# I2C_HANDLER.net
KiCad netlist of a schematic drawn in Altium Designer
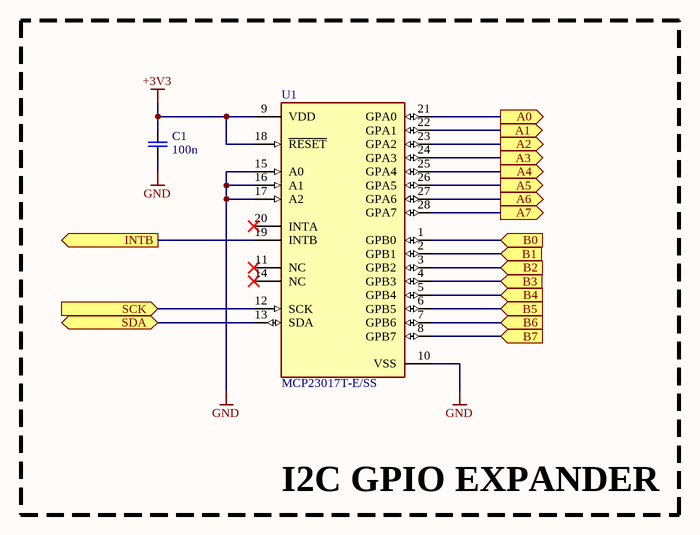
[diagram p0: I2C_HANDLER.SchDoc]

(export (version "E")
  (design (tool "Eeschema 10.0.6"))
  (components
    (comp (ref "C1")
      (value "100n")
      (footprint "C0603")
      (description "Generic 0603 SMD Ceramic Capacitor")
      (libsource (lib "PolSl Racing - Electrical") (part "Capacitor"))
    )
    (comp (ref "U1")
      (value "MCP23017T-E/SS")
      (footprint "FP-C04-073-IPC_C")
      (description "IC I/O EXPANDER 16BIT I2C 28SSOP")
      (libsource (lib "Altium Content Vault") (part "fef0bad8f325ed3b0116f589d195a7e"))
    )
  )
  (nets
    (net (code "1") (name "+3V3") (class "Default")
      (node (ref "C1") (pin "2") (pinfunction "2_2") (pintype "passive"))
      (node (ref "U1") (pin "18") (pinfunction "~{RESET}_18") (pintype "input"))
      (node (ref "U1") (pin "9") (pinfunction "VDD_9") (pintype "power_in"))
    )
    (net (code "2") (name "/A0") (class "Default")
      (node (ref "U1") (pin "21") (pinfunction "GPA0_21") (pintype "bidirectional"))
    )
    (net (code "3") (name "/A1") (class "Default")
      (node (ref "U1") (pin "22") (pinfunction "GPA1_22") (pintype "bidirectional"))
    )
    (net (code "4") (name "/A2") (class "Default")
      (node (ref "U1") (pin "23") (pinfunction "GPA2_23") (pintype "bidirectional"))
    )
    (net (code "5") (name "/A3") (class "Default")
      (node (ref "U1") (pin "24") (pinfunction "GPA3_24") (pintype "bidirectional"))
    )
    (net (code "6") (name "/A4") (class "Default")
      (node (ref "U1") (pin "25") (pinfunction "GPA4_25") (pintype "bidirectional"))
    )
    (net (code "7") (name "/A5") (class "Default")
      (node (ref "U1") (pin "26") (pinfunction "GPA5_26") (pintype "bidirectional"))
    )
    (net (code "8") (name "/A6") (class "Default")
      (node (ref "U1") (pin "27") (pinfunction "GPA6_27") (pintype "bidirectional"))
    )
    (net (code "9") (name "/A7") (class "Default")
      (node (ref "U1") (pin "28") (pinfunction "GPA7_28") (pintype "bidirectional"))
    )
    (net (code "10") (name "/B0") (class "Default")
      (node (ref "U1") (pin "1") (pinfunction "GPB0_1") (pintype "bidirectional"))
    )
    (net (code "11") (name "/B1") (class "Default")
      (node (ref "U1") (pin "2") (pinfunction "GPB1_2") (pintype "bidirectional"))
    )
    (net (code "12") (name "/B2") (class "Default")
      (node (ref "U1") (pin "3") (pinfunction "GPB2_3") (pintype "bidirectional"))
    )
    (net (code "13") (name "/B3") (class "Default")
      (node (ref "U1") (pin "4") (pinfunction "GPB3_4") (pintype "bidirectional"))
    )
    (net (code "14") (name "/B4") (class "Default")
      (node (ref "U1") (pin "5") (pinfunction "GPB4_5") (pintype "bidirectional"))
    )
    (net (code "15") (name "/B5") (class "Default")
      (node (ref "U1") (pin "6") (pinfunction "GPB5_6") (pintype "bidirectional"))
    )
    (net (code "16") (name "/B6") (class "Default")
      (node (ref "U1") (pin "7") (pinfunction "GPB6_7") (pintype "bidirectional"))
    )
    (net (code "17") (name "/B7") (class "Default")
      (node (ref "U1") (pin "8") (pinfunction "GPB7_8") (pintype "bidirectional"))
    )
    (net (code "18") (name "/INTB") (class "Default")
      (node (ref "U1") (pin "19") (pinfunction "INTB_19") (pintype "open_collector"))
    )
    (net (code "19") (name "/SCK") (class "Default")
      (node (ref "U1") (pin "12") (pinfunction "SCK_12") (pintype "input"))
    )
    (net (code "20") (name "/SDA") (class "Default")
      (node (ref "U1") (pin "13") (pinfunction "SDA_13") (pintype "bidirectional"))
    )
    (net (code "21") (name "GND") (class "Default")
      (node (ref "C1") (pin "1") (pinfunction "1_1") (pintype "passive"))
      (node (ref "U1") (pin "10") (pinfunction "VSS_10") (pintype "power_in"))
      (node (ref "U1") (pin "15") (pinfunction "A0_15") (pintype "input"))
      (node (ref "U1") (pin "16") (pinfunction "A1_16") (pintype "input"))
      (node (ref "U1") (pin "17") (pinfunction "A2_17") (pintype "input"))
    )
    (net (code "22") (name "unconnected-(U1-INTA-Pad20)") (class "Default")
      (node (ref "U1") (pin "20") (pinfunction "INTA_20") (pintype "open_collector+no_connect"))
    )
    (net (code "23") (name "unconnected-(U1-NC-Pad11)") (class "Default")
      (node (ref "U1") (pin "11") (pinfunction "NC_11") (pintype "passive+no_connect"))
    )
    (net (code "24") (name "unconnected-(U1-NC-Pad14)") (class "Default")
      (node (ref "U1") (pin "14") (pinfunction "NC_14") (pintype "passive+no_connect"))
    )
  )
)
